# Ethernet_POrts.net
KiCad netlist of a schematic drawn in EAGLE
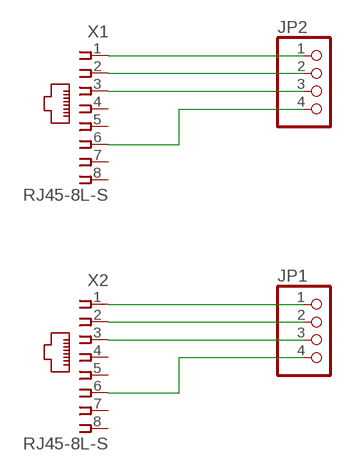
[diagram p0: schematic, sheet 1]

(export (version "E")
  (design (tool "Eeschema 10.0.6"))
  (components
    (comp (ref "JP1")
      (value "PINHD-1X4")
      (footprint "eagle-import:1X04")
      (libsource (lib "eagle-import") (part "PINHD-1X4"))
    )
    (comp (ref "JP2")
      (value "PINHD-1X4")
      (footprint "eagle-import:1X04")
      (libsource (lib "eagle-import") (part "PINHD-1X4"))
    )
    (comp (ref "X1")
      (value "RJ45-8L-S")
      (footprint "eagle-import:RJ45-NO-SHIELD")
      (fields (field (name "MF") "TYCO ELECTRONICS"))
      (libsource (lib "eagle-import") (part "RJ45-8L-S"))
    )
    (comp (ref "X2")
      (value "RJ45-8L-S")
      (footprint "eagle-import:RJ45-NO-SHIELD")
      (fields (field (name "MF") "TYCO ELECTRONICS"))
      (libsource (lib "eagle-import") (part "RJ45-8L-S"))
    )
  )
  (nets
    (net (code "1") (name "Net-(JP1-Pad1)") (class "Default")
      (node (ref "JP1") (pin "1") (pinfunction "1_1") (pintype "passive"))
      (node (ref "X2") (pin "1") (pinfunction "1_1") (pintype "passive"))
    )
    (net (code "2") (name "Net-(JP1-Pad2)") (class "Default")
      (node (ref "JP1") (pin "2") (pinfunction "2_2") (pintype "passive"))
      (node (ref "X2") (pin "2") (pinfunction "2_2") (pintype "passive"))
    )
    (net (code "3") (name "Net-(JP1-Pad3)") (class "Default")
      (node (ref "JP1") (pin "3") (pinfunction "3_3") (pintype "passive"))
      (node (ref "X2") (pin "3") (pinfunction "3_3") (pintype "passive"))
    )
    (net (code "4") (name "Net-(JP1-Pad4)") (class "Default")
      (node (ref "JP1") (pin "4") (pinfunction "4_4") (pintype "passive"))
      (node (ref "X2") (pin "6") (pinfunction "6_6") (pintype "passive"))
    )
    (net (code "5") (name "Net-(JP2-Pad1)") (class "Default")
      (node (ref "JP2") (pin "1") (pinfunction "1_1") (pintype "passive"))
      (node (ref "X1") (pin "1") (pinfunction "1_1") (pintype "passive"))
    )
    (net (code "6") (name "Net-(JP2-Pad2)") (class "Default")
      (node (ref "JP2") (pin "2") (pinfunction "2_2") (pintype "passive"))
      (node (ref "X1") (pin "2") (pinfunction "2_2") (pintype "passive"))
    )
    (net (code "7") (name "Net-(JP2-Pad3)") (class "Default")
      (node (ref "JP2") (pin "3") (pinfunction "3_3") (pintype "passive"))
      (node (ref "X1") (pin "3") (pinfunction "3_3") (pintype "passive"))
    )
    (net (code "8") (name "Net-(JP2-Pad4)") (class "Default")
      (node (ref "JP2") (pin "4") (pinfunction "4_4") (pintype "passive"))
      (node (ref "X1") (pin "6") (pinfunction "6_6") (pintype "passive"))
    )
    (net (code "9") (name "unconnected-(X1-Pad4)") (class "Default")
      (node (ref "X1") (pin "4") (pinfunction "4_4") (pintype "passive"))
    )
    (net (code "10") (name "unconnected-(X1-Pad5)") (class "Default")
      (node (ref "X1") (pin "5") (pinfunction "5_5") (pintype "passive"))
    )
    (net (code "11") (name "unconnected-(X1-Pad7)") (class "Default")
      (node (ref "X1") (pin "7") (pinfunction "7_7") (pintype "passive"))
    )
    (net (code "12") (name "unconnected-(X1-Pad8)") (class "Default")
      (node (ref "X1") (pin "8") (pinfunction "8_8") (pintype "passive"))
    )
    (net (code "13") (name "unconnected-(X2-Pad4)") (class "Default")
      (node (ref "X2") (pin "4") (pinfunction "4_4") (pintype "passive"))
    )
    (net (code "14") (name "unconnected-(X2-Pad5)") (class "Default")
      (node (ref "X2") (pin "5") (pinfunction "5_5") (pintype "passive"))
    )
    (net (code "15") (name "unconnected-(X2-Pad7)") (class "Default")
      (node (ref "X2") (pin "7") (pinfunction "7_7") (pintype "passive"))
    )
    (net (code "16") (name "unconnected-(X2-Pad8)") (class "Default")
      (node (ref "X2") (pin "8") (pinfunction "8_8") (pintype "passive"))
    )
  )
)
